# turbo.net
KiCad netlist of a schematic drawn in EAGLE
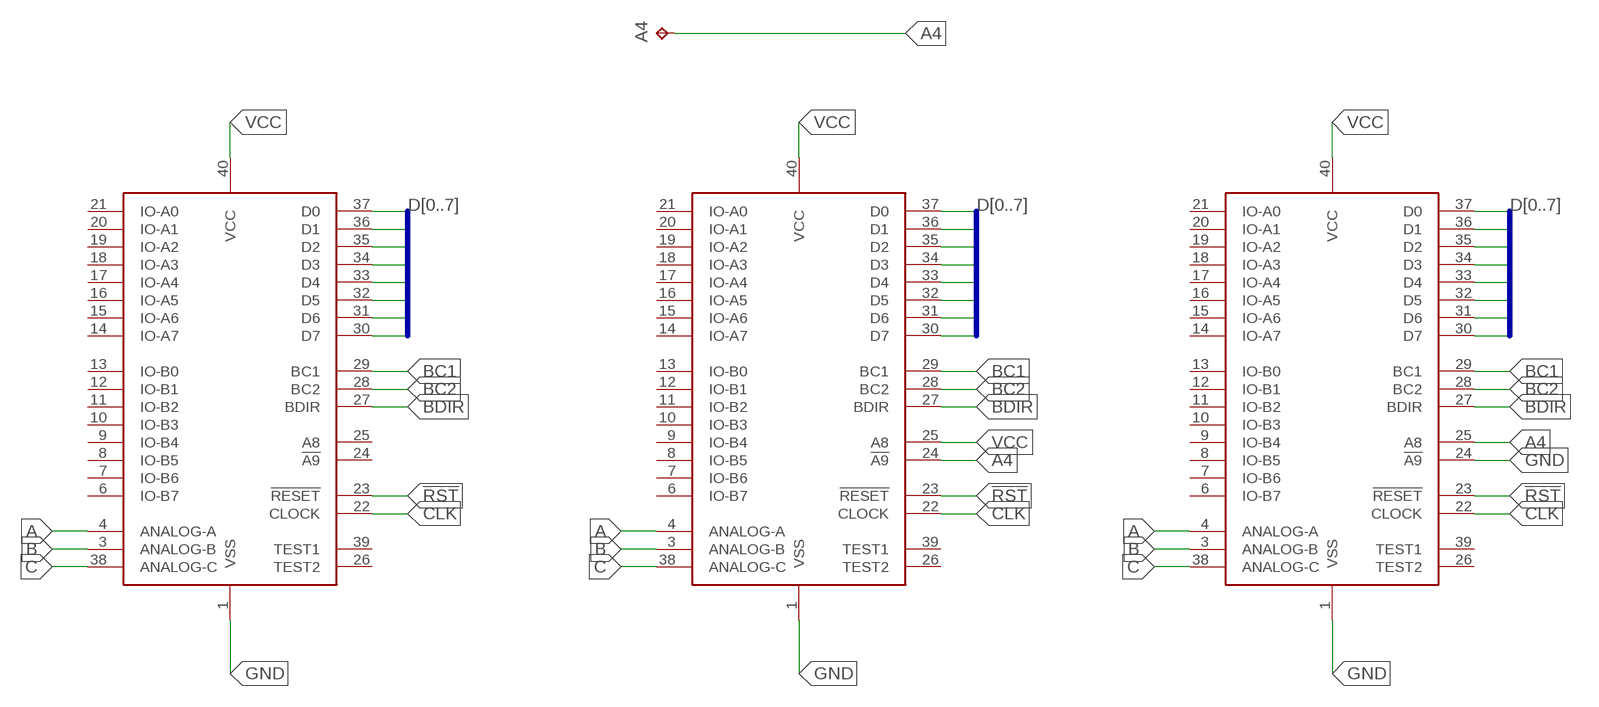
[diagram p0: schematic, sheet 1]

(export (version "E")
  (design (tool "Eeschema 10.0.6"))
  (components
    (comp (ref "A4")
      (value "TPB1,27")
      (footprint "eagle-import:B1,27")
      (libsource (lib "eagle-import") (part "TPB1,27"))
    )
    (comp (ref "AY1")
      (value "AY-3-8910")
      (footprint "eagle-import:DIL40")
      (libsource (lib "eagle-import") (part "AY-3-8910"))
    )
    (comp (ref "AY2")
      (value "AY-3-8910")
      (footprint "eagle-import:DIL40")
      (libsource (lib "eagle-import") (part "AY-3-8910"))
    )
    (comp (ref "INPUT")
      (value "AY-3-8910")
      (footprint "eagle-import:DIL40")
      (libsource (lib "eagle-import") (part "AY-3-8910"))
    )
  )
  (nets
    (net (code "1") (name "/D0") (class "Default")
      (node (ref "AY1") (pin "37") (pinfunction "D0_37") (pintype "input"))
      (node (ref "AY2") (pin "37") (pinfunction "D0_37") (pintype "input"))
      (node (ref "INPUT") (pin "37") (pinfunction "D0_37") (pintype "input"))
    )
    (net (code "2") (name "/D1") (class "Default")
      (node (ref "AY1") (pin "36") (pinfunction "D1_36") (pintype "input"))
      (node (ref "AY2") (pin "36") (pinfunction "D1_36") (pintype "input"))
      (node (ref "INPUT") (pin "36") (pinfunction "D1_36") (pintype "input"))
    )
    (net (code "3") (name "/D2") (class "Default")
      (node (ref "AY1") (pin "35") (pinfunction "D2_35") (pintype "input"))
      (node (ref "AY2") (pin "35") (pinfunction "D2_35") (pintype "input"))
      (node (ref "INPUT") (pin "35") (pinfunction "D2_35") (pintype "input"))
    )
    (net (code "4") (name "/D3") (class "Default")
      (node (ref "AY1") (pin "34") (pinfunction "D3_34") (pintype "input"))
      (node (ref "AY2") (pin "34") (pinfunction "D3_34") (pintype "input"))
      (node (ref "INPUT") (pin "34") (pinfunction "D3_34") (pintype "input"))
    )
    (net (code "5") (name "/D4") (class "Default")
      (node (ref "AY1") (pin "33") (pinfunction "D4_33") (pintype "input"))
      (node (ref "AY2") (pin "33") (pinfunction "D4_33") (pintype "input"))
      (node (ref "INPUT") (pin "33") (pinfunction "D4_33") (pintype "input"))
    )
    (net (code "6") (name "/D5") (class "Default")
      (node (ref "AY1") (pin "32") (pinfunction "D5_32") (pintype "input"))
      (node (ref "AY2") (pin "32") (pinfunction "D5_32") (pintype "input"))
      (node (ref "INPUT") (pin "32") (pinfunction "D5_32") (pintype "input"))
    )
    (net (code "7") (name "/D6") (class "Default")
      (node (ref "AY1") (pin "31") (pinfunction "D6_31") (pintype "input"))
      (node (ref "AY2") (pin "31") (pinfunction "D6_31") (pintype "input"))
      (node (ref "INPUT") (pin "31") (pinfunction "D6_31") (pintype "input"))
    )
    (net (code "8") (name "/D7") (class "Default")
      (node (ref "AY1") (pin "30") (pinfunction "D7_30") (pintype "input"))
      (node (ref "AY2") (pin "30") (pinfunction "D7_30") (pintype "input"))
      (node (ref "INPUT") (pin "30") (pinfunction "D7_30") (pintype "input"))
    )
    (net (code "9") (name "/~{RST}") (class "Default")
      (node (ref "AY1") (pin "23") (pinfunction "~{RESET}_23") (pintype "input"))
      (node (ref "AY2") (pin "23") (pinfunction "~{RESET}_23") (pintype "input"))
      (node (ref "INPUT") (pin "23") (pinfunction "~{RESET}_23") (pintype "input"))
    )
    (net (code "10") (name "A") (class "Default")
      (node (ref "AY1") (pin "4") (pinfunction "ANALOG-A_4") (pintype "output"))
      (node (ref "AY2") (pin "4") (pinfunction "ANALOG-A_4") (pintype "output"))
      (node (ref "INPUT") (pin "4") (pinfunction "ANALOG-A_4") (pintype "output"))
    )
    (net (code "11") (name "A4") (class "Default")
      (node (ref "A4") (pin "TP") (pinfunction "TP_TP") (pintype "input"))
      (node (ref "AY1") (pin "24") (pinfunction "~{A9}_24") (pintype "input"))
      (node (ref "AY2") (pin "25") (pinfunction "A8_25") (pintype "input"))
    )
    (net (code "12") (name "B") (class "Default")
      (node (ref "AY1") (pin "3") (pinfunction "ANALOG-B_3") (pintype "output"))
      (node (ref "AY2") (pin "3") (pinfunction "ANALOG-B_3") (pintype "output"))
      (node (ref "INPUT") (pin "3") (pinfunction "ANALOG-B_3") (pintype "output"))
    )
    (net (code "13") (name "BC1") (class "Default")
      (node (ref "AY1") (pin "29") (pinfunction "BC1_29") (pintype "input"))
      (node (ref "AY2") (pin "29") (pinfunction "BC1_29") (pintype "input"))
      (node (ref "INPUT") (pin "29") (pinfunction "BC1_29") (pintype "input"))
    )
    (net (code "14") (name "BC2") (class "Default")
      (node (ref "AY1") (pin "28") (pinfunction "BC2_28") (pintype "input"))
      (node (ref "AY2") (pin "28") (pinfunction "BC2_28") (pintype "input"))
      (node (ref "INPUT") (pin "28") (pinfunction "BC2_28") (pintype "input"))
    )
    (net (code "15") (name "BDIR") (class "Default")
      (node (ref "AY1") (pin "27") (pinfunction "BDIR_27") (pintype "input"))
      (node (ref "AY2") (pin "27") (pinfunction "BDIR_27") (pintype "input"))
      (node (ref "INPUT") (pin "27") (pinfunction "BDIR_27") (pintype "input"))
    )
    (net (code "16") (name "C") (class "Default")
      (node (ref "AY1") (pin "38") (pinfunction "ANALOG-C_38") (pintype "output"))
      (node (ref "AY2") (pin "38") (pinfunction "ANALOG-C_38") (pintype "output"))
      (node (ref "INPUT") (pin "38") (pinfunction "ANALOG-C_38") (pintype "output"))
    )
    (net (code "17") (name "CLK") (class "Default")
      (node (ref "AY1") (pin "22") (pinfunction "CLOCK_22") (pintype "input"))
      (node (ref "AY2") (pin "22") (pinfunction "CLOCK_22") (pintype "input"))
      (node (ref "INPUT") (pin "22") (pinfunction "CLOCK_22") (pintype "input"))
    )
    (net (code "18") (name "GND") (class "Default")
      (node (ref "AY1") (pin "1") (pinfunction "VSS_1") (pintype "power_in"))
      (node (ref "AY2") (pin "1") (pinfunction "VSS_1") (pintype "power_in"))
      (node (ref "AY2") (pin "24") (pinfunction "~{A9}_24") (pintype "input"))
      (node (ref "INPUT") (pin "1") (pinfunction "VSS_1") (pintype "power_in"))
    )
    (net (code "19") (name "VCC") (class "Default")
      (node (ref "AY1") (pin "25") (pinfunction "A8_25") (pintype "input"))
      (node (ref "AY1") (pin "40") (pinfunction "VCC_40") (pintype "power_in"))
      (node (ref "AY2") (pin "40") (pinfunction "VCC_40") (pintype "power_in"))
      (node (ref "INPUT") (pin "40") (pinfunction "VCC_40") (pintype "power_in"))
    )
    (net (code "20") (name "unconnected-(AY1-IO-A0-Pad21)") (class "Default")
      (node (ref "AY1") (pin "21") (pinfunction "IO-A0_21") (pintype "bidirectional"))
    )
    (net (code "21") (name "unconnected-(AY1-IO-A1-Pad20)") (class "Default")
      (node (ref "AY1") (pin "20") (pinfunction "IO-A1_20") (pintype "bidirectional"))
    )
    (net (code "22") (name "unconnected-(AY1-IO-A2-Pad19)") (class "Default")
      (node (ref "AY1") (pin "19") (pinfunction "IO-A2_19") (pintype "bidirectional"))
    )
    (net (code "23") (name "unconnected-(AY1-IO-A3-Pad18)") (class "Default")
      (node (ref "AY1") (pin "18") (pinfunction "IO-A3_18") (pintype "bidirectional"))
    )
    (net (code "24") (name "unconnected-(AY1-IO-A4-Pad17)") (class "Default")
      (node (ref "AY1") (pin "17") (pinfunction "IO-A4_17") (pintype "bidirectional"))
    )
    (net (code "25") (name "unconnected-(AY1-IO-A5-Pad16)") (class "Default")
      (node (ref "AY1") (pin "16") (pinfunction "IO-A5_16") (pintype "bidirectional"))
    )
    (net (code "26") (name "unconnected-(AY1-IO-A6-Pad15)") (class "Default")
      (node (ref "AY1") (pin "15") (pinfunction "IO-A6_15") (pintype "bidirectional"))
    )
    (net (code "27") (name "unconnected-(AY1-IO-A7-Pad14)") (class "Default")
      (node (ref "AY1") (pin "14") (pinfunction "IO-A7_14") (pintype "bidirectional"))
    )
    (net (code "28") (name "unconnected-(AY1-IO-B0-Pad13)") (class "Default")
      (node (ref "AY1") (pin "13") (pinfunction "IO-B0_13") (pintype "bidirectional"))
    )
    (net (code "29") (name "unconnected-(AY1-IO-B1-Pad12)") (class "Default")
      (node (ref "AY1") (pin "12") (pinfunction "IO-B1_12") (pintype "bidirectional"))
    )
    (net (code "30") (name "unconnected-(AY1-IO-B2-Pad11)") (class "Default")
      (node (ref "AY1") (pin "11") (pinfunction "IO-B2_11") (pintype "bidirectional"))
    )
    (net (code "31") (name "unconnected-(AY1-IO-B3-Pad10)") (class "Default")
      (node (ref "AY1") (pin "10") (pinfunction "IO-B3_10") (pintype "bidirectional"))
    )
    (net (code "32") (name "unconnected-(AY1-IO-B4-Pad9)") (class "Default")
      (node (ref "AY1") (pin "9") (pinfunction "IO-B4_9") (pintype "bidirectional"))
    )
    (net (code "33") (name "unconnected-(AY1-IO-B5-Pad8)") (class "Default")
      (node (ref "AY1") (pin "8") (pinfunction "IO-B5_8") (pintype "bidirectional"))
    )
    (net (code "34") (name "unconnected-(AY1-IO-B6-Pad7)") (class "Default")
      (node (ref "AY1") (pin "7") (pinfunction "IO-B6_7") (pintype "bidirectional"))
    )
    (net (code "35") (name "unconnected-(AY1-IO-B7-Pad6)") (class "Default")
      (node (ref "AY1") (pin "6") (pinfunction "IO-B7_6") (pintype "bidirectional"))
    )
    (net (code "36") (name "unconnected-(AY1-TEST1-Pad39)") (class "Default")
      (node (ref "AY1") (pin "39") (pinfunction "TEST1_39") (pintype "input"))
    )
    (net (code "37") (name "unconnected-(AY1-TEST2-Pad26)") (class "Default")
      (node (ref "AY1") (pin "26") (pinfunction "TEST2_26") (pintype "output"))
    )
    (net (code "38") (name "unconnected-(AY2-IO-A0-Pad21)") (class "Default")
      (node (ref "AY2") (pin "21") (pinfunction "IO-A0_21") (pintype "bidirectional"))
    )
    (net (code "39") (name "unconnected-(AY2-IO-A1-Pad20)") (class "Default")
      (node (ref "AY2") (pin "20") (pinfunction "IO-A1_20") (pintype "bidirectional"))
    )
    (net (code "40") (name "unconnected-(AY2-IO-A2-Pad19)") (class "Default")
      (node (ref "AY2") (pin "19") (pinfunction "IO-A2_19") (pintype "bidirectional"))
    )
    (net (code "41") (name "unconnected-(AY2-IO-A3-Pad18)") (class "Default")
      (node (ref "AY2") (pin "18") (pinfunction "IO-A3_18") (pintype "bidirectional"))
    )
    (net (code "42") (name "unconnected-(AY2-IO-A4-Pad17)") (class "Default")
      (node (ref "AY2") (pin "17") (pinfunction "IO-A4_17") (pintype "bidirectional"))
    )
    (net (code "43") (name "unconnected-(AY2-IO-A5-Pad16)") (class "Default")
      (node (ref "AY2") (pin "16") (pinfunction "IO-A5_16") (pintype "bidirectional"))
    )
    (net (code "44") (name "unconnected-(AY2-IO-A6-Pad15)") (class "Default")
      (node (ref "AY2") (pin "15") (pinfunction "IO-A6_15") (pintype "bidirectional"))
    )
    (net (code "45") (name "unconnected-(AY2-IO-A7-Pad14)") (class "Default")
      (node (ref "AY2") (pin "14") (pinfunction "IO-A7_14") (pintype "bidirectional"))
    )
    (net (code "46") (name "unconnected-(AY2-IO-B0-Pad13)") (class "Default")
      (node (ref "AY2") (pin "13") (pinfunction "IO-B0_13") (pintype "bidirectional"))
    )
    (net (code "47") (name "unconnected-(AY2-IO-B1-Pad12)") (class "Default")
      (node (ref "AY2") (pin "12") (pinfunction "IO-B1_12") (pintype "bidirectional"))
    )
    (net (code "48") (name "unconnected-(AY2-IO-B2-Pad11)") (class "Default")
      (node (ref "AY2") (pin "11") (pinfunction "IO-B2_11") (pintype "bidirectional"))
    )
    (net (code "49") (name "unconnected-(AY2-IO-B3-Pad10)") (class "Default")
      (node (ref "AY2") (pin "10") (pinfunction "IO-B3_10") (pintype "bidirectional"))
    )
    (net (code "50") (name "unconnected-(AY2-IO-B4-Pad9)") (class "Default")
      (node (ref "AY2") (pin "9") (pinfunction "IO-B4_9") (pintype "bidirectional"))
    )
    (net (code "51") (name "unconnected-(AY2-IO-B5-Pad8)") (class "Default")
      (node (ref "AY2") (pin "8") (pinfunction "IO-B5_8") (pintype "bidirectional"))
    )
    (net (code "52") (name "unconnected-(AY2-IO-B6-Pad7)") (class "Default")
      (node (ref "AY2") (pin "7") (pinfunction "IO-B6_7") (pintype "bidirectional"))
    )
    (net (code "53") (name "unconnected-(AY2-IO-B7-Pad6)") (class "Default")
      (node (ref "AY2") (pin "6") (pinfunction "IO-B7_6") (pintype "bidirectional"))
    )
    (net (code "54") (name "unconnected-(AY2-TEST1-Pad39)") (class "Default")
      (node (ref "AY2") (pin "39") (pinfunction "TEST1_39") (pintype "input"))
    )
    (net (code "55") (name "unconnected-(AY2-TEST2-Pad26)") (class "Default")
      (node (ref "AY2") (pin "26") (pinfunction "TEST2_26") (pintype "output"))
    )
    (net (code "56") (name "unconnected-(INPUT-A8-Pad25)") (class "Default")
      (node (ref "INPUT") (pin "25") (pinfunction "A8_25") (pintype "input"))
    )
    (net (code "57") (name "unconnected-(INPUT-IO-A0-Pad21)") (class "Default")
      (node (ref "INPUT") (pin "21") (pinfunction "IO-A0_21") (pintype "bidirectional"))
    )
    (net (code "58") (name "unconnected-(INPUT-IO-A1-Pad20)") (class "Default")
      (node (ref "INPUT") (pin "20") (pinfunction "IO-A1_20") (pintype "bidirectional"))
    )
    (net (code "59") (name "unconnected-(INPUT-IO-A2-Pad19)") (class "Default")
      (node (ref "INPUT") (pin "19") (pinfunction "IO-A2_19") (pintype "bidirectional"))
    )
    (net (code "60") (name "unconnected-(INPUT-IO-A3-Pad18)") (class "Default")
      (node (ref "INPUT") (pin "18") (pinfunction "IO-A3_18") (pintype "bidirectional"))
    )
    (net (code "61") (name "unconnected-(INPUT-IO-A4-Pad17)") (class "Default")
      (node (ref "INPUT") (pin "17") (pinfunction "IO-A4_17") (pintype "bidirectional"))
    )
    (net (code "62") (name "unconnected-(INPUT-IO-A5-Pad16)") (class "Default")
      (node (ref "INPUT") (pin "16") (pinfunction "IO-A5_16") (pintype "bidirectional"))
    )
    (net (code "63") (name "unconnected-(INPUT-IO-A6-Pad15)") (class "Default")
      (node (ref "INPUT") (pin "15") (pinfunction "IO-A6_15") (pintype "bidirectional"))
    )
    (net (code "64") (name "unconnected-(INPUT-IO-A7-Pad14)") (class "Default")
      (node (ref "INPUT") (pin "14") (pinfunction "IO-A7_14") (pintype "bidirectional"))
    )
    (net (code "65") (name "unconnected-(INPUT-IO-B0-Pad13)") (class "Default")
      (node (ref "INPUT") (pin "13") (pinfunction "IO-B0_13") (pintype "bidirectional"))
    )
    (net (code "66") (name "unconnected-(INPUT-IO-B1-Pad12)") (class "Default")
      (node (ref "INPUT") (pin "12") (pinfunction "IO-B1_12") (pintype "bidirectional"))
    )
    (net (code "67") (name "unconnected-(INPUT-IO-B2-Pad11)") (class "Default")
      (node (ref "INPUT") (pin "11") (pinfunction "IO-B2_11") (pintype "bidirectional"))
    )
    (net (code "68") (name "unconnected-(INPUT-IO-B3-Pad10)") (class "Default")
      (node (ref "INPUT") (pin "10") (pinfunction "IO-B3_10") (pintype "bidirectional"))
    )
    (net (code "69") (name "unconnected-(INPUT-IO-B4-Pad9)") (class "Default")
      (node (ref "INPUT") (pin "9") (pinfunction "IO-B4_9") (pintype "bidirectional"))
    )
    (net (code "70") (name "unconnected-(INPUT-IO-B5-Pad8)") (class "Default")
      (node (ref "INPUT") (pin "8") (pinfunction "IO-B5_8") (pintype "bidirectional"))
    )
    (net (code "71") (name "unconnected-(INPUT-IO-B6-Pad7)") (class "Default")
      (node (ref "INPUT") (pin "7") (pinfunction "IO-B6_7") (pintype "bidirectional"))
    )
    (net (code "72") (name "unconnected-(INPUT-IO-B7-Pad6)") (class "Default")
      (node (ref "INPUT") (pin "6") (pinfunction "IO-B7_6") (pintype "bidirectional"))
    )
    (net (code "73") (name "unconnected-(INPUT-TEST1-Pad39)") (class "Default")
      (node (ref "INPUT") (pin "39") (pinfunction "TEST1_39") (pintype "input"))
    )
    (net (code "74") (name "unconnected-(INPUT-TEST2-Pad26)") (class "Default")
      (node (ref "INPUT") (pin "26") (pinfunction "TEST2_26") (pintype "output"))
    )
    (net (code "75") (name "unconnected-(INPUT-~{A9}-Pad24)") (class "Default")
      (node (ref "INPUT") (pin "24") (pinfunction "~{A9}_24") (pintype "input"))
    )
  )
)
